# 02_Power.net
KiCad netlist of a schematic drawn in Altium Designer
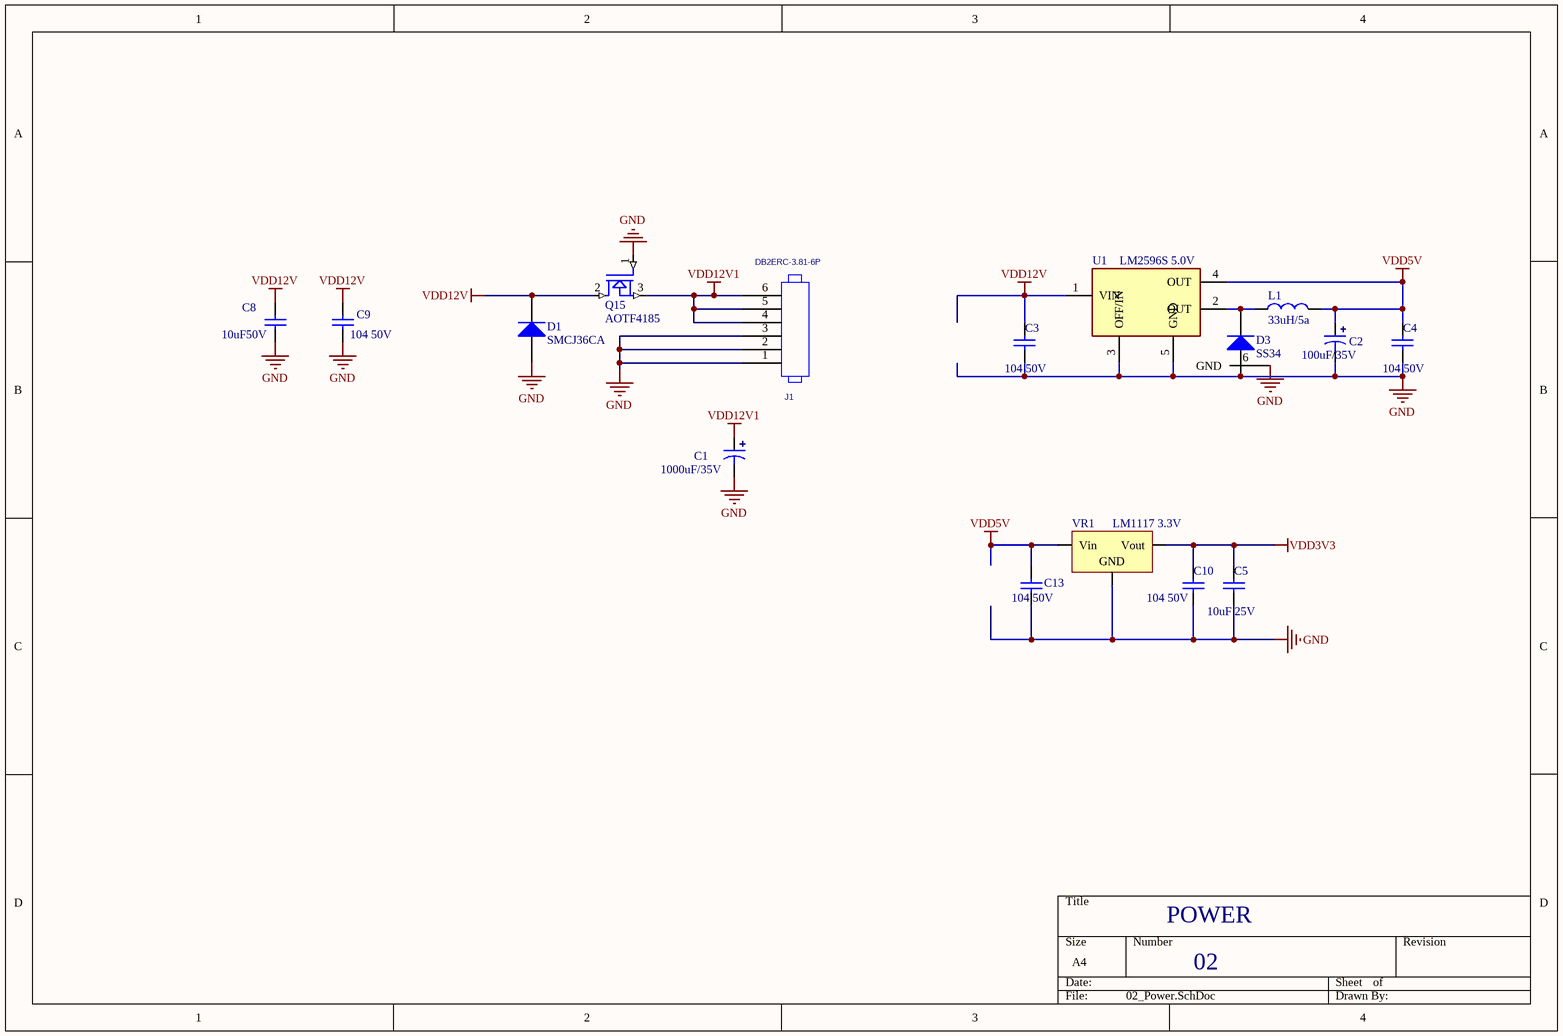
[diagram p0: 02_Power.SchDoc]

(export (version "E")
  (design (tool "Eeschema 10.0.6"))
  (components
    (comp (ref "C1")
      (value "1000uF/35V")
      (footprint "10*16")
      (description "电解电容")
      (libsource (lib "XiaoyI") (part "CAP2"))
    )
    (comp (ref "C2")
      (value "100uF/35V")
      (footprint "6*8")
      (description "电解电容")
      (libsource (lib "XiaoyI") (part "CAP2"))
    )
    (comp (ref "C3")
      (value "104 50V")
      (footprint "SMD-0603C")
      (description "贴片电容 10%")
      (libsource (lib "XiaoyI") (part "CAP4"))
    )
    (comp (ref "C4")
      (value "104 50V")
      (footprint "SMD-0603C")
      (description "贴片电容 10%")
      (libsource (lib "XiaoyI") (part "CAP4"))
    )
    (comp (ref "C5")
      (value "10uF 25V")
      (footprint "SMD-0805C")
      (description "贴片电容 20%")
      (libsource (lib "XiaoyI") (part "CAP4"))
    )
    (comp (ref "C8")
      (value "10uF50V")
      (footprint "SMD-0805C")
      (description "贴片电容 10%")
      (libsource (lib "XiaoyI") (part "CAP4"))
    )
    (comp (ref "C9")
      (value "104 50V")
      (footprint "SMD-0603C")
      (description "贴片电容 10%")
      (libsource (lib "XiaoyI") (part "CAP4"))
    )
    (comp (ref "C10")
      (value "104 50V")
      (footprint "SMD-0603C")
      (description "贴片电容 10%")
      (libsource (lib "XiaoyI") (part "CAP4"))
    )
    (comp (ref "C13")
      (value "104 50V")
      (footprint "SMD-0603C")
      (description "贴片电容 10%")
      (libsource (lib "XiaoyI") (part "CAP4"))
    )
    (comp (ref "D1")
      (value "SMCJ36CA")
      (footprint "Pcblib_20110825:SMC")
      (libsource (lib "Sch_library") (part "DIODE"))
    )
    (comp (ref "D3") (value "SS34") (footprint "SMA") (libsource (lib "Sch_library") (part "DIODE")))
    (comp (ref "J1")
      (value "DB2ERC-3.81-6P")
      (footprint "VH-AW-3.96*6P")
      (fields (field (name "Comment") "HEADER_6"))
      (libsource (lib "liujingtao_V1.0") (part "HEADER_6"))
    )
    (comp (ref "L1") (value "33uH/5a") (footprint "CDRH-127") (libsource (lib "Sch_library") (part "IND")))
    (comp (ref "Q15")
      (value "AOTF4185")
      (footprint "Pcblib_20110825:to220")
      (description "MOSFET N")
      (libsource (lib "XiaoyI") (part "MOSFET N"))
    )
    (comp (ref "U1")
      (value "LM2596S 5.0V")
      (footprint "TO-263-5")
      (libsource (lib "Sch_library") (part "LM2596"))
    )
    (comp (ref "VR1")
      (value "LM1117 3.3V")
      (footprint "SOT223")
      (description "三端稳压器")
      (libsource (lib "XiaoyI") (part "LM1117"))
    )
  )
  (nets
    (net (code "1") (name "GND") (class "Default")
      (node (ref "C1") (pin "2") (pinfunction "2_2") (pintype "passive"))
      (node (ref "C10") (pin "1") (pinfunction "1_1") (pintype "passive"))
      (node (ref "C13") (pin "1") (pinfunction "1_1") (pintype "passive"))
      (node (ref "C2") (pin "2") (pinfunction "2_2") (pintype "passive"))
      (node (ref "C3") (pin "1") (pinfunction "1_1") (pintype "passive"))
      (node (ref "C4") (pin "1") (pinfunction "1_1") (pintype "passive"))
      (node (ref "C5") (pin "1") (pinfunction "1_1") (pintype "passive"))
      (node (ref "C8") (pin "1") (pinfunction "1_1") (pintype "passive"))
      (node (ref "C9") (pin "1") (pinfunction "1_1") (pintype "passive"))
      (node (ref "D1") (pin "1") (pinfunction "A_1") (pintype "passive"))
      (node (ref "D3") (pin "1") (pinfunction "A_1") (pintype "passive"))
      (node (ref "J1") (pin "1") (pinfunction "1_1") (pintype "passive"))
      (node (ref "J1") (pin "2") (pinfunction "2_2") (pintype "passive"))
      (node (ref "J1") (pin "3") (pinfunction "3_3") (pintype "passive"))
      (node (ref "Q15") (pin "1") (pinfunction "G_1") (pintype "input"))
      (node (ref "U1") (pin "3") (pinfunction "OFF/IN_3") (pintype "passive"))
      (node (ref "U1") (pin "5") (pinfunction "GND_5") (pintype "passive"))
      (node (ref "U1") (pin "6") (pinfunction "GND_6") (pintype "passive"))
      (node (ref "VR1") (pin "1") (pinfunction "GND_1") (pintype "passive"))
    )
    (net (code "2") (name "Net-(D3-K)") (class "Default")
      (node (ref "D3") (pin "2") (pinfunction "K_2") (pintype "passive"))
      (node (ref "L1") (pin "1") (pinfunction "1_1") (pintype "passive"))
      (node (ref "U1") (pin "2") (pinfunction "OUT_2") (pintype "passive"))
    )
    (net (code "3") (name "VDD3V3") (class "Default")
      (node (ref "C10") (pin "2") (pinfunction "2_2") (pintype "passive"))
      (node (ref "C5") (pin "2") (pinfunction "2_2") (pintype "passive"))
      (node (ref "VR1") (pin "2") (pinfunction "Vout_2") (pintype "passive"))
    )
    (net (code "4") (name "VDD5V") (class "Default")
      (node (ref "C13") (pin "2") (pinfunction "2_2") (pintype "passive"))
      (node (ref "C2") (pin "1") (pinfunction "1_1") (pintype "passive"))
      (node (ref "C4") (pin "2") (pinfunction "2_2") (pintype "passive"))
      (node (ref "L1") (pin "2") (pinfunction "2_2") (pintype "passive"))
      (node (ref "U1") (pin "4") (pinfunction "OUT_4") (pintype "passive"))
      (node (ref "VR1") (pin "3") (pinfunction "Vin_3") (pintype "passive"))
    )
    (net (code "5") (name "VDD12V") (class "Default")
      (node (ref "C3") (pin "2") (pinfunction "2_2") (pintype "passive"))
      (node (ref "C8") (pin "2") (pinfunction "2_2") (pintype "passive"))
      (node (ref "C9") (pin "2") (pinfunction "2_2") (pintype "passive"))
      (node (ref "D1") (pin "2") (pinfunction "K_2") (pintype "passive"))
      (node (ref "Q15") (pin "2") (pinfunction "D_2") (pintype "input"))
      (node (ref "U1") (pin "1") (pinfunction "VIN_1") (pintype "passive"))
    )
    (net (code "6") (name "VDD12V1") (class "Default")
      (node (ref "C1") (pin "1") (pinfunction "1_1") (pintype "passive"))
      (node (ref "J1") (pin "4") (pinfunction "4_4") (pintype "passive"))
      (node (ref "J1") (pin "5") (pinfunction "5_5") (pintype "passive"))
      (node (ref "J1") (pin "6") (pinfunction "6_6") (pintype "passive"))
      (node (ref "Q15") (pin "3") (pinfunction "S_3") (pintype "output"))
    )
  )
)
